# Arduino.net
KiCad netlist of a schematic drawn in EAGLE
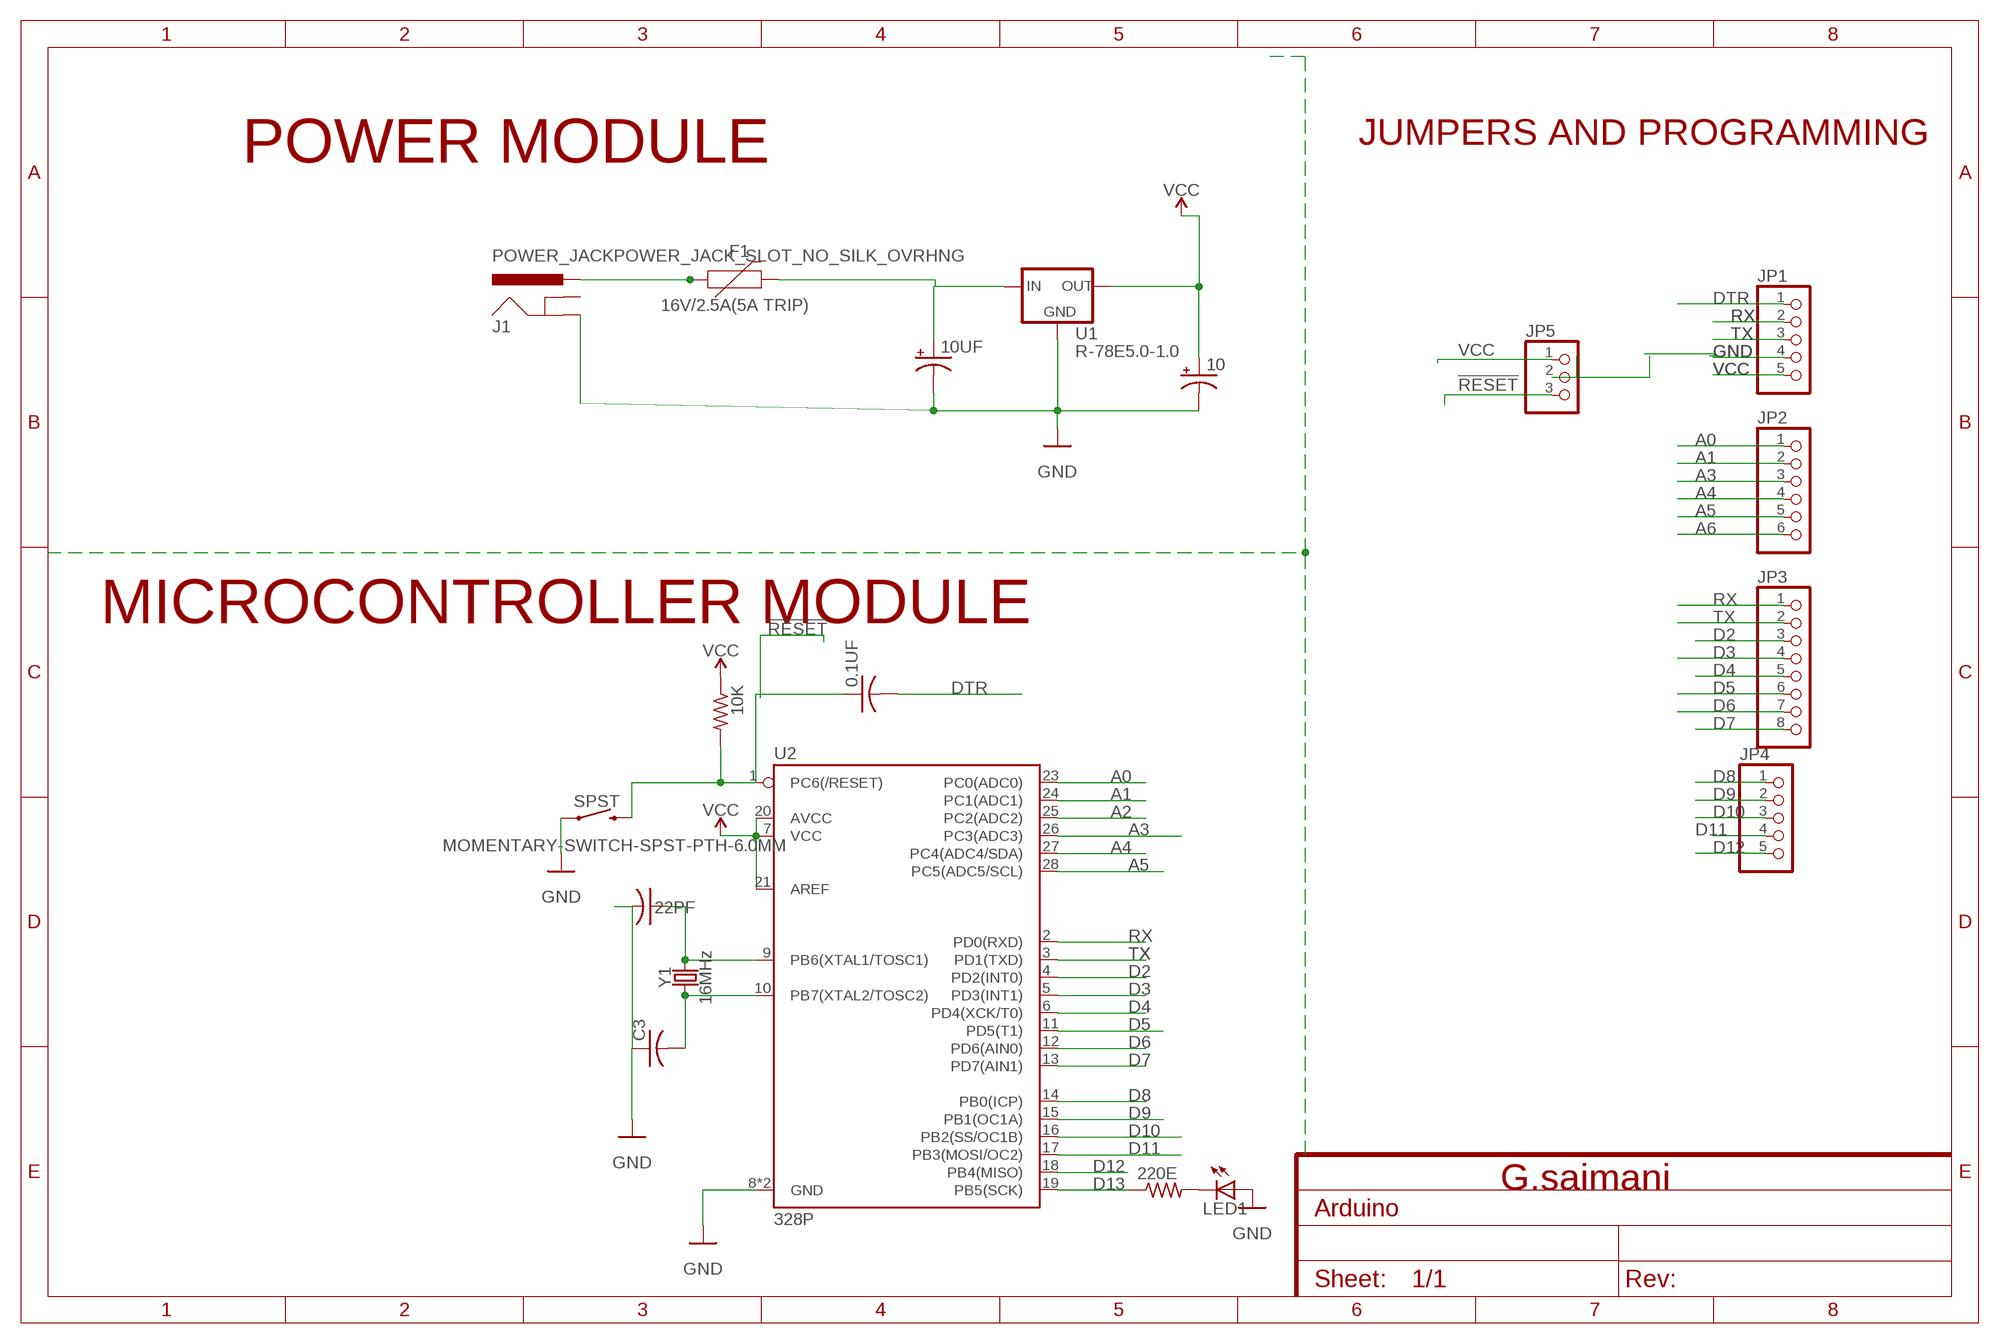
[diagram p0: schematic, sheet 1]

(export (version "E")
  (design (tool "Eeschema 10.0.6"))
  (components
    (comp (ref "0.1UF")
      (value "C-US025-024X044")
      (footprint "eagle-import:C025-024X044")
      (libsource (lib "eagle-import") (part "C-US025-024X044"))
    )
    (comp (ref "10")
      (value "CPOL-USE2-5")
      (footprint "eagle-import:E2-5")
      (libsource (lib "eagle-import") (part "CPOL-USE2-5"))
    )
    (comp (ref "10K")
      (value "R-US_0204/7")
      (footprint "eagle-import:0204_7")
      (libsource (lib "eagle-import") (part "R-US_0204/7"))
    )
    (comp (ref "10UF")
      (value "CPOL-USE2-5")
      (footprint "eagle-import:E2-5")
      (libsource (lib "eagle-import") (part "CPOL-USE2-5"))
    )
    (comp (ref "22PF")
      (value "C-US025-024X044")
      (footprint "eagle-import:C025-024X044")
      (libsource (lib "eagle-import") (part "C-US025-024X044"))
    )
    (comp (ref "220E")
      (value "R-US_0207/7")
      (footprint "eagle-import:0207_7")
      (libsource (lib "eagle-import") (part "R-US_0207/7"))
    )
    (comp (ref "C3")
      (value "C-US025-024X044")
      (footprint "eagle-import:C025-024X044")
      (libsource (lib "eagle-import") (part "C-US025-024X044"))
    )
    (comp (ref "F1")
      (value "16V/2.5A(5A TRIP)")
      (footprint "eagle-import:1812")
      (libsource (lib "eagle-import") (part "PPTC_16V_2.5A"))
    )
    (comp (ref "J1")
      (value "POWER_JACKPOWER_JACK_SLOT_NO_SILK_OVRHNG")
      (footprint "eagle-import:POWER_JACK_PTH_SLOT_NO_OVRHNG_SILK")
      (libsource (lib "eagle-import") (part "POWER_JACKPOWER_JACK_SLOT_NO_SILK_OVRHNG"))
    )
    (comp (ref "JP1")
      (value "PINHD-1X5")
      (footprint "eagle-import:1X05")
      (libsource (lib "eagle-import") (part "PINHD-1X5"))
    )
    (comp (ref "JP2")
      (value "PINHD-1X6")
      (footprint "eagle-import:1X06")
      (libsource (lib "eagle-import") (part "PINHD-1X6"))
    )
    (comp (ref "JP3")
      (value "PINHD-1X8")
      (footprint "eagle-import:1X08")
      (libsource (lib "eagle-import") (part "PINHD-1X8"))
    )
    (comp (ref "JP4")
      (value "PINHD-1X5")
      (footprint "eagle-import:1X05")
      (libsource (lib "eagle-import") (part "PINHD-1X5"))
    )
    (comp (ref "JP5")
      (value "PINHD-1X3")
      (footprint "eagle-import:1X03")
      (libsource (lib "eagle-import") (part "PINHD-1X3"))
    )
    (comp (ref "LED1")
      (value "LED")
      (footprint "eagle-import:SMARTLED-TTW")
      (libsource (lib "eagle-import") (part "LED"))
    )
    (comp (ref "SPST")
      (value "MOMENTARY-SWITCH-SPST-PTH-6.0MM")
      (footprint "eagle-import:TACTILE_SWITCH_PTH_6.0MM")
      (libsource (lib "eagle-import") (part "MOMENTARY-SWITCH-SPST-PTH-6.0MM"))
    )
    (comp (ref "U1")
      (value "R-78E5.0-1.0")
      (footprint "eagle-import:DC-DC_CONVERTER_78XX")
      (libsource (lib "eagle-import") (part "R-78E5.0-1.0"))
    )
    (comp (ref "U2")
      (value "328P")
      (footprint "eagle-import:DIP28")
      (libsource (lib "eagle-import") (part "ATMEGA328P_PDIP"))
    )
    (comp (ref "Y1")
      (value "16MHz")
      (footprint "eagle-import:HC49US")
      (libsource (lib "eagle-import") (part "CRYSTAL-16MHZPTH-HC49US"))
    )
  )
  (nets
    (net (code "1") (name "/A0") (class "Default")
      (node (ref "JP2") (pin "1") (pinfunction "1_1") (pintype "passive"))
      (node (ref "U2") (pin "23") (pinfunction "PC0(ADC0)_23") (pintype "bidirectional"))
    )
    (net (code "2") (name "/A1") (class "Default")
      (node (ref "JP2") (pin "2") (pinfunction "2_2") (pintype "passive"))
      (node (ref "U2") (pin "24") (pinfunction "PC1(ADC1)_24") (pintype "bidirectional"))
    )
    (net (code "3") (name "/A2") (class "Default")
      (node (ref "U2") (pin "25") (pinfunction "PC2(ADC2)_25") (pintype "bidirectional"))
    )
    (net (code "4") (name "/A3") (class "Default")
      (node (ref "JP2") (pin "3") (pinfunction "3_3") (pintype "passive"))
      (node (ref "U2") (pin "26") (pinfunction "PC3(ADC3)_26") (pintype "bidirectional"))
    )
    (net (code "5") (name "/A4") (class "Default")
      (node (ref "JP2") (pin "4") (pinfunction "4_4") (pintype "passive"))
      (node (ref "U2") (pin "27") (pinfunction "PC4(ADC4/SDA)_27") (pintype "bidirectional"))
    )
    (net (code "6") (name "/A5") (class "Default")
      (node (ref "JP2") (pin "5") (pinfunction "5_5") (pintype "passive"))
      (node (ref "U2") (pin "28") (pinfunction "PC5(ADC5/SCL)_28") (pintype "bidirectional"))
    )
    (net (code "7") (name "/A6") (class "Default")
      (node (ref "JP2") (pin "6") (pinfunction "6_6") (pintype "passive"))
    )
    (net (code "8") (name "/D2") (class "Default")
      (node (ref "JP3") (pin "3") (pinfunction "3_3") (pintype "passive"))
      (node (ref "U2") (pin "4") (pinfunction "PD2(INT0)_4") (pintype "bidirectional"))
    )
    (net (code "9") (name "/D3") (class "Default")
      (node (ref "JP3") (pin "4") (pinfunction "4_4") (pintype "passive"))
      (node (ref "U2") (pin "5") (pinfunction "PD3(INT1)_5") (pintype "bidirectional"))
    )
    (net (code "10") (name "/D4") (class "Default")
      (node (ref "JP3") (pin "5") (pinfunction "5_5") (pintype "passive"))
      (node (ref "U2") (pin "6") (pinfunction "PD4(XCK/T0)_6") (pintype "bidirectional"))
    )
    (net (code "11") (name "/D5") (class "Default")
      (node (ref "JP3") (pin "6") (pinfunction "6_6") (pintype "passive"))
      (node (ref "U2") (pin "11") (pinfunction "PD5(T1)_11") (pintype "bidirectional"))
    )
    (net (code "12") (name "/D6") (class "Default")
      (node (ref "JP3") (pin "7") (pinfunction "7_7") (pintype "passive"))
      (node (ref "U2") (pin "12") (pinfunction "PD6(AIN0)_12") (pintype "bidirectional"))
    )
    (net (code "13") (name "/D7") (class "Default")
      (node (ref "JP3") (pin "8") (pinfunction "8_8") (pintype "passive"))
      (node (ref "U2") (pin "13") (pinfunction "PD7(AIN1)_13") (pintype "bidirectional"))
    )
    (net (code "14") (name "/D8") (class "Default")
      (node (ref "JP4") (pin "1") (pinfunction "1_1") (pintype "passive"))
      (node (ref "U2") (pin "14") (pinfunction "PB0(ICP)_14") (pintype "bidirectional"))
    )
    (net (code "15") (name "/D9") (class "Default")
      (node (ref "JP4") (pin "2") (pinfunction "2_2") (pintype "passive"))
      (node (ref "U2") (pin "15") (pinfunction "PB1(OC1A)_15") (pintype "bidirectional"))
    )
    (net (code "16") (name "/D10") (class "Default")
      (node (ref "JP4") (pin "3") (pinfunction "3_3") (pintype "passive"))
      (node (ref "U2") (pin "16") (pinfunction "PB2(SS/OC1B)_16") (pintype "bidirectional"))
    )
    (net (code "17") (name "/D11") (class "Default")
      (node (ref "JP4") (pin "4") (pinfunction "4_4") (pintype "passive"))
      (node (ref "U2") (pin "17") (pinfunction "PB3(MOSI/OC2)_17") (pintype "bidirectional"))
    )
    (net (code "18") (name "/D12") (class "Default")
      (node (ref "JP4") (pin "5") (pinfunction "5_5") (pintype "passive"))
      (node (ref "U2") (pin "18") (pinfunction "PB4(MISO)_18") (pintype "bidirectional"))
    )
    (net (code "19") (name "/D13") (class "Default")
      (node (ref "220E") (pin "1") (pinfunction "1_1") (pintype "passive"))
      (node (ref "U2") (pin "19") (pinfunction "PB5(SCK)_19") (pintype "bidirectional"))
    )
    (net (code "20") (name "/DTR") (class "Default")
      (node (ref "0.1UF") (pin "2") (pinfunction "2_2") (pintype "passive"))
      (node (ref "JP1") (pin "1") (pinfunction "1_1") (pintype "passive"))
    )
    (net (code "21") (name "/RX") (class "Default")
      (node (ref "JP1") (pin "2") (pinfunction "2_2") (pintype "passive"))
      (node (ref "JP3") (pin "1") (pinfunction "1_1") (pintype "passive"))
      (node (ref "U2") (pin "2") (pinfunction "PD0(RXD)_2") (pintype "bidirectional"))
    )
    (net (code "22") (name "/TX") (class "Default")
      (node (ref "JP1") (pin "3") (pinfunction "3_3") (pintype "passive"))
      (node (ref "JP3") (pin "2") (pinfunction "2_2") (pintype "passive"))
      (node (ref "U2") (pin "3") (pinfunction "PD1(TXD)_3") (pintype "bidirectional"))
    )
    (net (code "23") (name "/~{RESET}") (class "Default")
      (node (ref "JP5") (pin "3") (pinfunction "3_3") (pintype "passive"))
    )
    (net (code "24") (name "GND") (class "Default")
      (node (ref "10") (pin "-") (pinfunction "-_-") (pintype "passive"))
      (node (ref "10UF") (pin "-") (pinfunction "-_-") (pintype "passive"))
      (node (ref "22PF") (pin "2") (pinfunction "2_2") (pintype "passive"))
      (node (ref "C3") (pin "1") (pinfunction "1_1") (pintype "passive"))
      (node (ref "J1") (pin "GND") (pinfunction "GND_GND") (pintype "bidirectional"))
      (node (ref "JP1") (pin "4") (pinfunction "4_4") (pintype "passive"))
      (node (ref "LED1") (pin "A@1") (pinfunction "A_A@1") (pintype "passive"))
      (node (ref "SPST") (pin "1") (pinfunction "1_1") (pintype "passive"))
      (node (ref "U1") (pin "GND") (pinfunction "GND_GND") (pintype "input"))
      (node (ref "U2") (pin "22") (pinfunction "GND_22") (pintype "bidirectional"))
      (node (ref "U2") (pin "8") (pinfunction "GND_8") (pintype "bidirectional"))
    )
    (net (code "25") (name "Net-(F1-Pad1)") (class "Default")
      (node (ref "F1") (pin "1") (pinfunction "1_1") (pintype "bidirectional"))
      (node (ref "J1") (pin "PWR") (pinfunction "PWR_PWR") (pintype "bidirectional"))
    )
    (net (code "26") (name "Net-(LED1-C)") (class "Default")
      (node (ref "220E") (pin "2") (pinfunction "2_2") (pintype "passive"))
      (node (ref "LED1") (pin "C@1") (pinfunction "C_C@1") (pintype "passive"))
    )
    (net (code "27") (name "Net-(SPST-2)") (class "Default")
      (node (ref "0.1UF") (pin "1") (pinfunction "1_1") (pintype "passive"))
      (node (ref "10K") (pin "2") (pinfunction "2_2") (pintype "passive"))
      (node (ref "SPST") (pin "3") (pinfunction "2_3") (pintype "passive"))
      (node (ref "U2") (pin "1") (pinfunction "PC6(/RESET)_1") (pintype "bidirectional"))
    )
    (net (code "28") (name "Net-(U1-IN)") (class "Default")
      (node (ref "10UF") (pin "+") (pinfunction "+_+") (pintype "passive"))
      (node (ref "U1") (pin "VIN") (pinfunction "IN_VIN") (pintype "input"))
    )
    (net (code "29") (name "Net-(U2-PB6(XTAL1{slash}TOSC1))") (class "Default")
      (node (ref "22PF") (pin "1") (pinfunction "1_1") (pintype "passive"))
      (node (ref "U2") (pin "9") (pinfunction "PB6(XTAL1/TOSC1)_9") (pintype "bidirectional"))
      (node (ref "Y1") (pin "2") (pinfunction "2_2") (pintype "passive"))
    )
    (net (code "30") (name "Net-(U2-PB7(XTAL2{slash}TOSC2))") (class "Default")
      (node (ref "C3") (pin "2") (pinfunction "2_2") (pintype "passive"))
      (node (ref "U2") (pin "10") (pinfunction "PB7(XTAL2/TOSC2)_10") (pintype "bidirectional"))
      (node (ref "Y1") (pin "1") (pinfunction "1_1") (pintype "passive"))
    )
    (net (code "31") (name "VCC") (class "Default")
      (node (ref "10") (pin "+") (pinfunction "+_+") (pintype "passive"))
      (node (ref "10K") (pin "1") (pinfunction "1_1") (pintype "passive"))
      (node (ref "JP1") (pin "5") (pinfunction "5_5") (pintype "passive"))
      (node (ref "JP5") (pin "1") (pinfunction "1_1") (pintype "passive"))
      (node (ref "U1") (pin "VOUT") (pinfunction "OUT_VOUT") (pintype "passive"))
      (node (ref "U2") (pin "20") (pinfunction "AVCC_20") (pintype "bidirectional"))
      (node (ref "U2") (pin "21") (pinfunction "AREF_21") (pintype "bidirectional"))
      (node (ref "U2") (pin "7") (pinfunction "VCC_7") (pintype "bidirectional"))
    )
    (net (code "32") (name "unconnected-(F1-Pad2)") (class "Default")
      (node (ref "F1") (pin "2") (pinfunction "2_2") (pintype "bidirectional"))
    )
    (net (code "33") (name "unconnected-(J1-PadGNDBREAK)") (class "Default")
      (node (ref "J1") (pin "GNDBREAK") (pinfunction "GNDBREAK_GNDBREAK") (pintype "bidirectional"))
    )
    (net (code "34") (name "unconnected-(JP5-Pad2)") (class "Default")
      (node (ref "JP5") (pin "2") (pinfunction "2_2") (pintype "passive"))
    )
  )
)
